# Musa_Schematic.net
KiCad netlist of a schematic drawn in Altium Designer
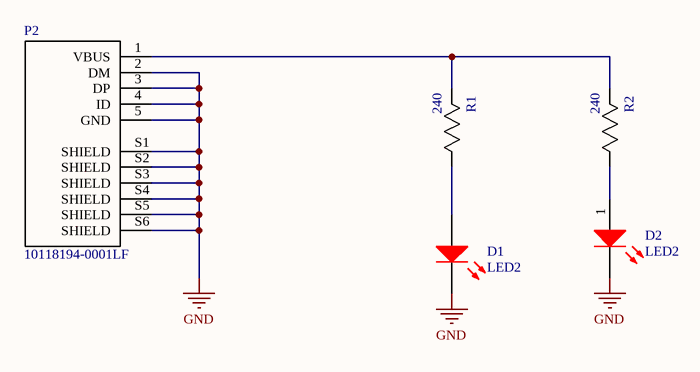
[diagram p0: Musa_Schematic.SchDoc]

(export (version "E")
  (design (tool "Eeschema 10.0.6"))
  (components
    (comp (ref "D1")
      (value "LED2")
      (footprint "3.2X1.6X1.1")
      (description "Typical RED, GREEN, YELLOW, AMBER GaAs LED")
      (libsource (lib "") (part "LED RED SMD_1"))
    )
    (comp (ref "D2")
      (value "LED2")
      (footprint "3.2X1.6X1.1")
      (description "Typical RED, GREEN, YELLOW, AMBER GaAs LED")
      (libsource (lib "AltiumLibraries") (part "LED RED SMD"))
    )
    (comp (ref "P2")
      (value "10118194-0001LF")
      (footprint "USB Micro B Receptacle")
      (description "USB - micro B USB 2.0 Receptacle Connector 5 Position Surface Mount, Right Angle; Through Hole")
      (fields (field (name "MF") "Amphenol ICC (FCI)"))
      (libsource (lib "AltiumLibraries") (part "USB Micro B Receptacle"))
    )
    (comp (ref "R1")
      (value "240")
      (footprint "0805")
      (description "RES SMD 240 OHM 5% 1/8W 0805")
      (fields (field (name "TOLERANCE") "5%"))
      (libsource (lib "AltiumLibraries") (part "RES 240.0 1/8W"))
    )
    (comp (ref "R2")
      (value "240")
      (footprint "0805")
      (description "RES SMD 240 OHM 5% 1/8W 0805")
      (fields (field (name "TOLERANCE") "5%"))
      (libsource (lib "") (part "RES 240.0 1/8W_1"))
    )
  )
  (nets
    (net (code "1") (name "GND") (class "Default")
      (node (ref "D1") (pin "2") (pinfunction "K_2") (pintype "passive"))
      (node (ref "D2") (pin "2") (pinfunction "K_2") (pintype "passive"))
      (node (ref "P2") (pin "2") (pinfunction "DM_2") (pintype "passive"))
      (node (ref "P2") (pin "3") (pinfunction "DP_3") (pintype "passive"))
      (node (ref "P2") (pin "4") (pinfunction "ID_4") (pintype "passive"))
      (node (ref "P2") (pin "5") (pinfunction "GND_5") (pintype "passive"))
      (node (ref "P2") (pin "S1") (pinfunction "SHIELD_S1") (pintype "passive"))
      (node (ref "P2") (pin "S2") (pinfunction "SHIELD_S2") (pintype "passive"))
      (node (ref "P2") (pin "S3") (pinfunction "SHIELD_S3") (pintype "passive"))
      (node (ref "P2") (pin "S4") (pinfunction "SHIELD_S4") (pintype "passive"))
      (node (ref "P2") (pin "S5") (pinfunction "SHIELD_S5") (pintype "passive"))
      (node (ref "P2") (pin "S6") (pinfunction "SHIELD_S6") (pintype "passive"))
    )
    (net (code "2") (name "Net-(D1-A)") (class "Default")
      (node (ref "D1") (pin "1") (pinfunction "A_1") (pintype "passive"))
      (node (ref "R1") (pin "1") (pinfunction "R1_1") (pintype "passive"))
    )
    (net (code "3") (name "Net-(D2-A)") (class "Default")
      (node (ref "D2") (pin "1") (pinfunction "A_1") (pintype "passive"))
      (node (ref "R2") (pin "1") (pinfunction "R1_1") (pintype "passive"))
    )
    (net (code "4") (name "Net-(P2-VBUS)") (class "Default")
      (node (ref "P2") (pin "1") (pinfunction "VBUS_1") (pintype "passive"))
      (node (ref "R1") (pin "2") (pinfunction "R2_2") (pintype "passive"))
      (node (ref "R2") (pin "2") (pinfunction "R2_2") (pintype "passive"))
    )
  )
)
